# P03_Processor_1_of_3_JTAG_Header.net
KiCad netlist of a schematic drawn in Altium Designer
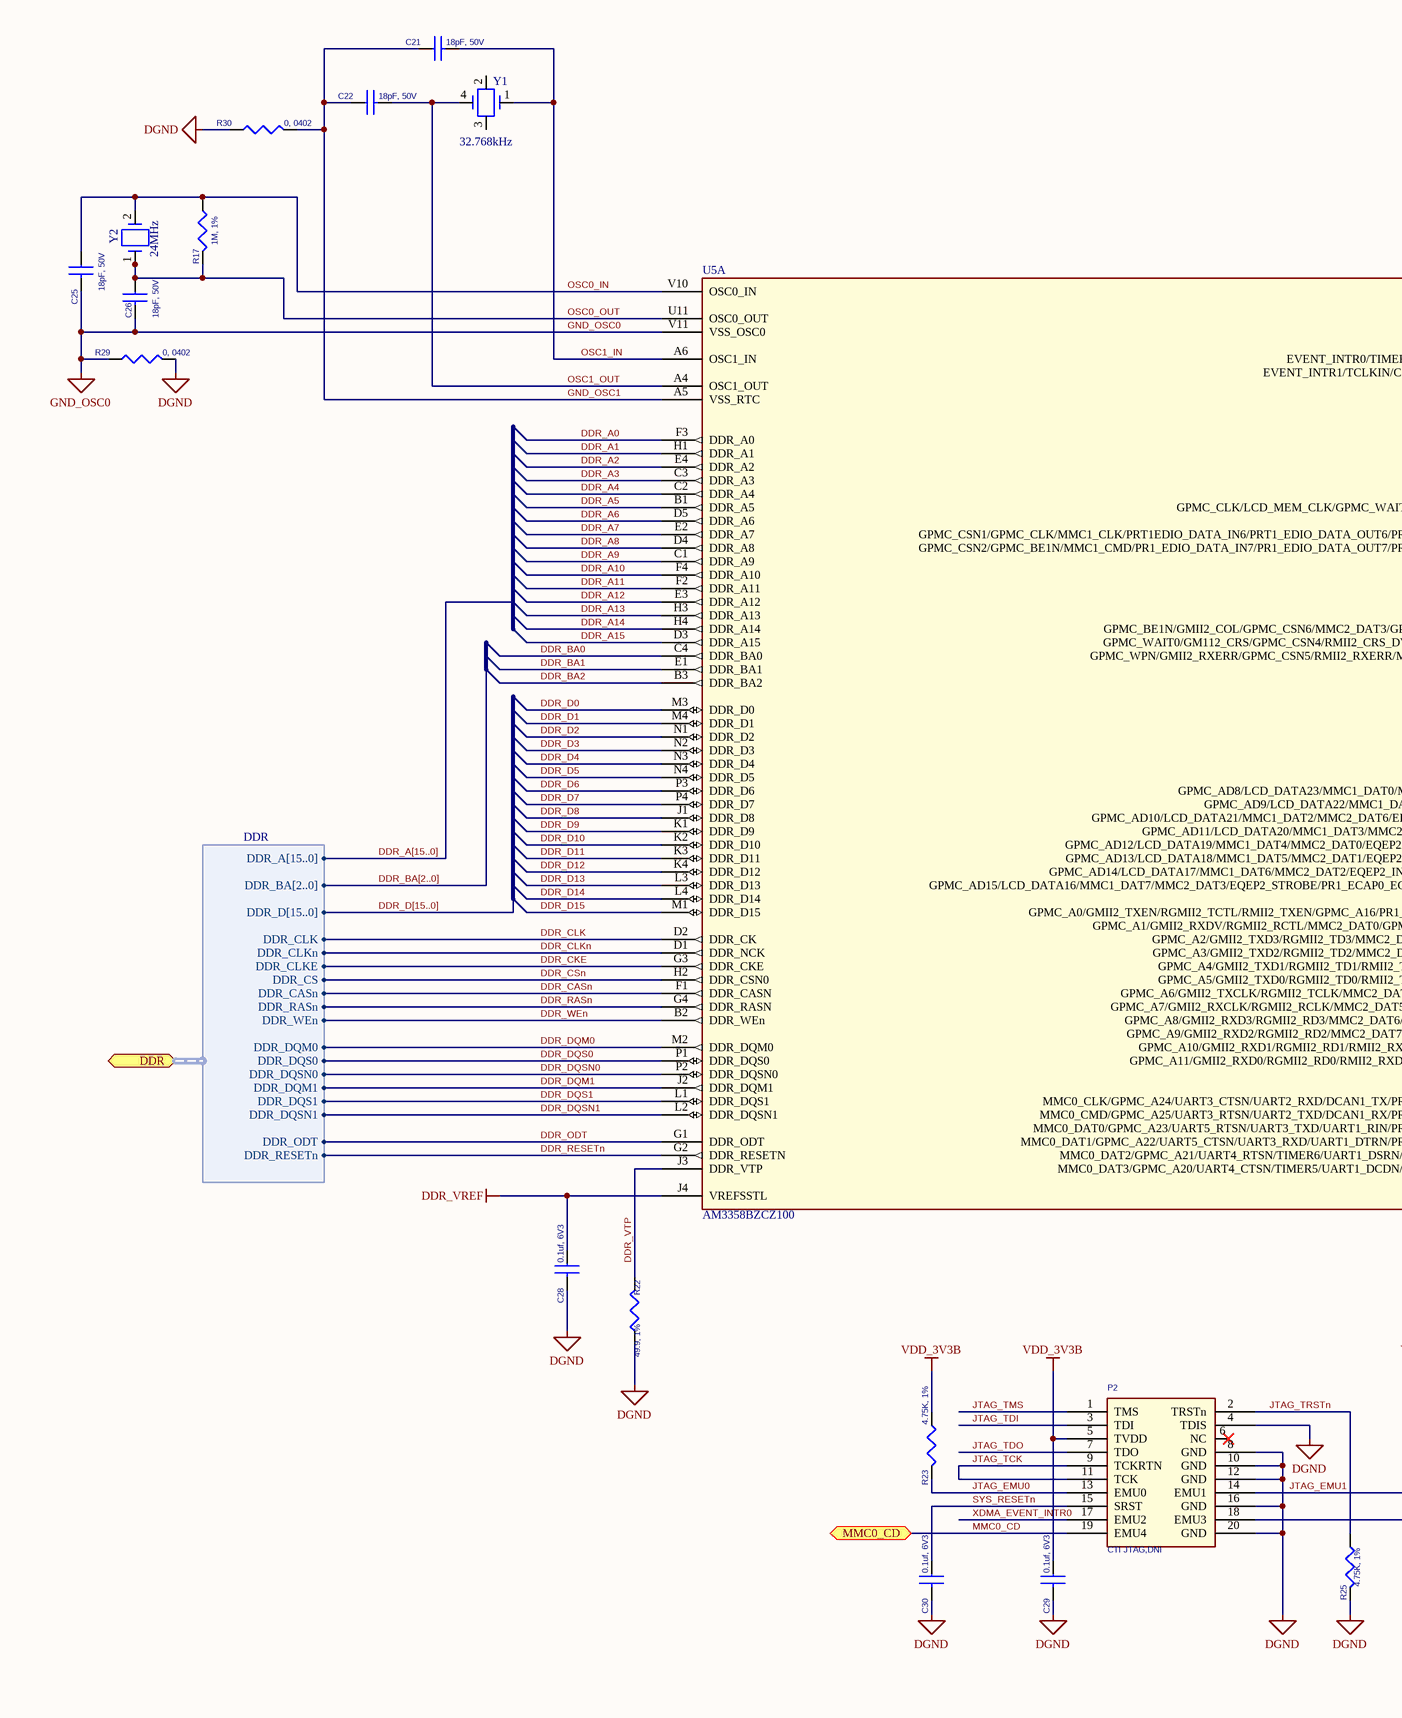
[diagram p0: P03_Processor 1 of 3, JTAG Header.SchDoc, left]
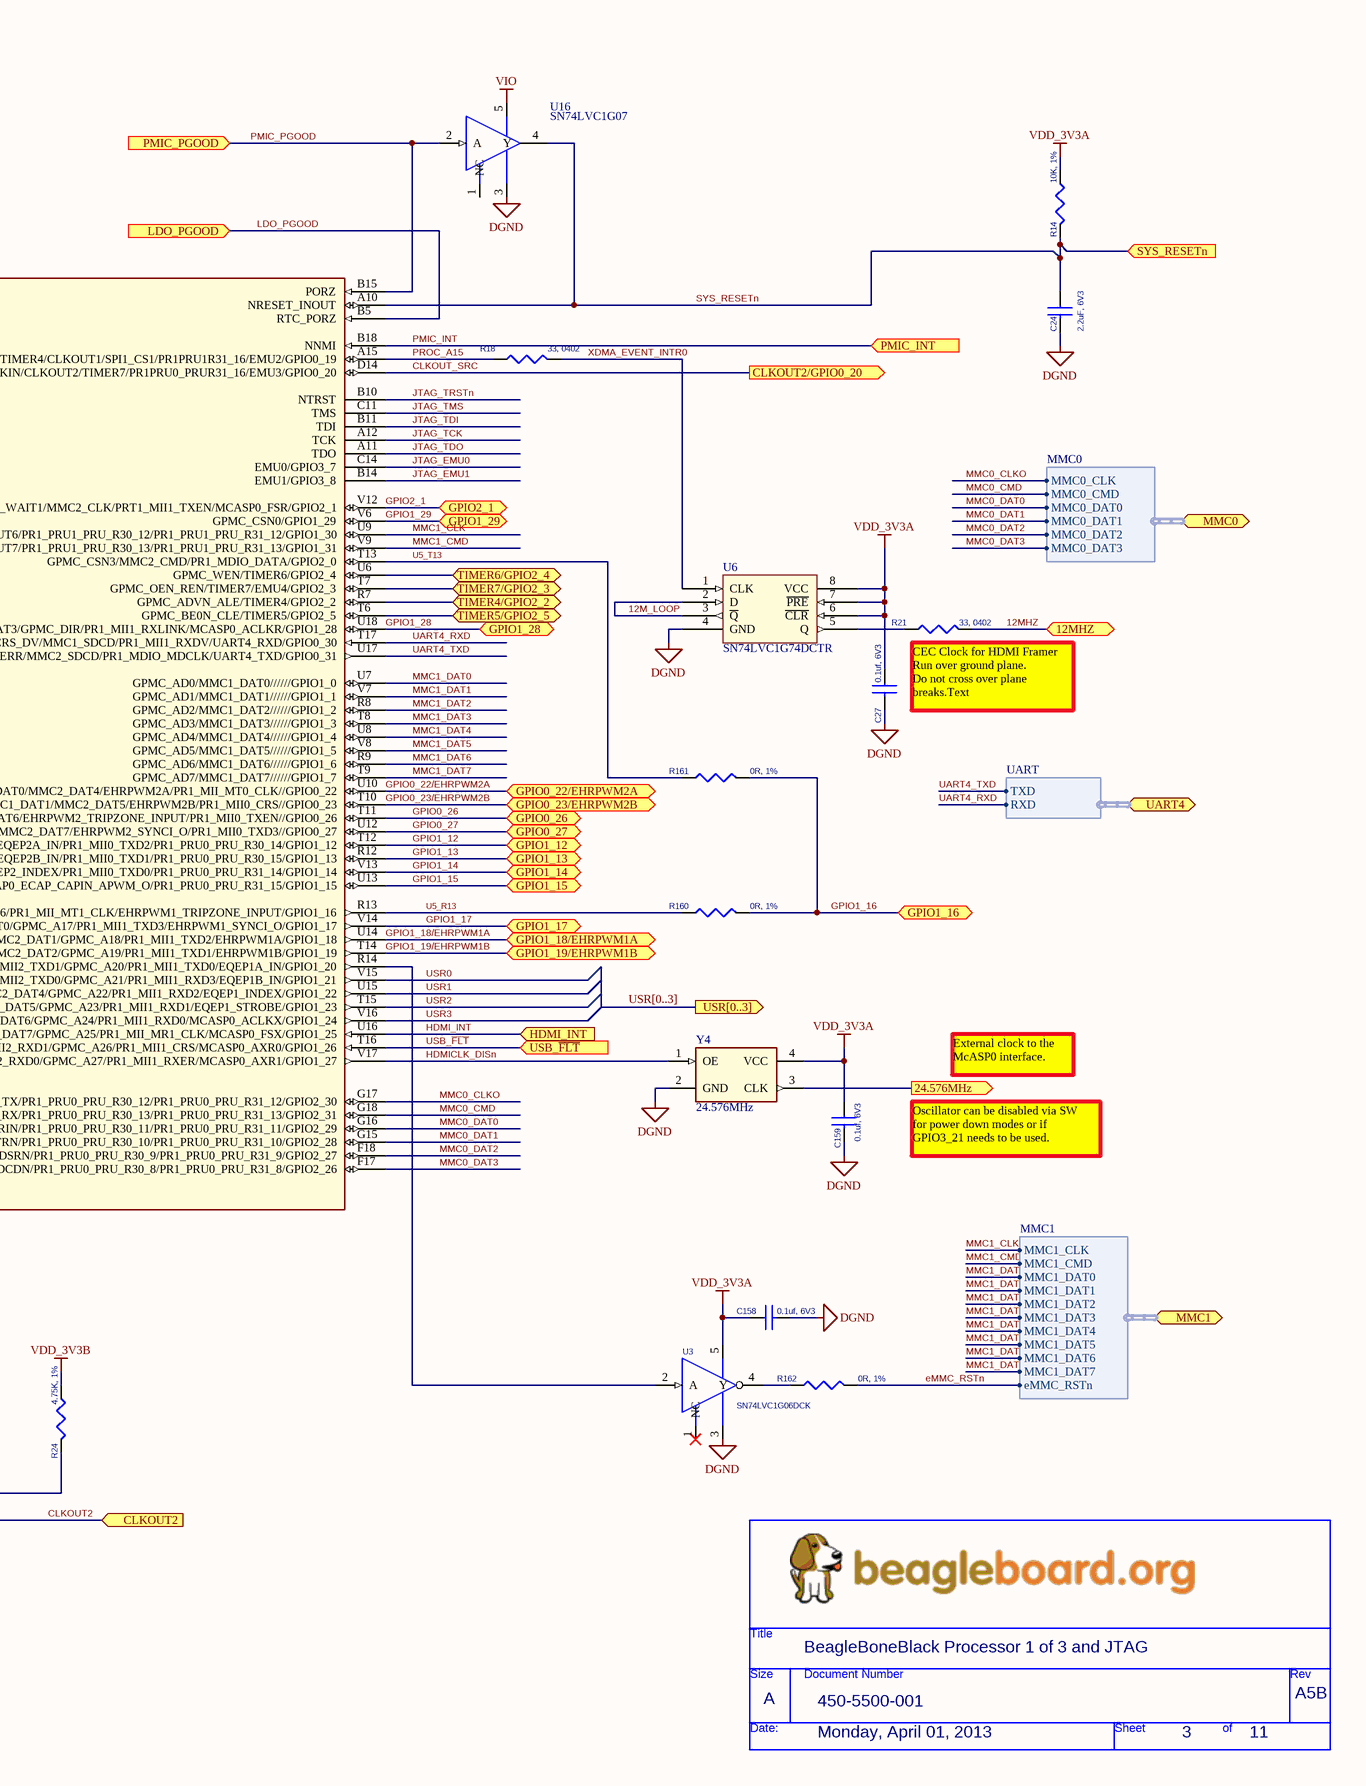
[diagram p1: P03_Processor 1 of 3, JTAG Header.SchDoc, right]

(export (version "E")
  (design (tool "Eeschema 10.0.6"))
  (components
    (comp (ref "C21")
      (value "18pF, 50V")
      (footprint "402")
      (description "CAP CER 18PF 50V 5% NP0 0402")
      (fields
        (field (name "MANUFACTURER") "TDK Corporation")
        (field (name "MANUFACTURER PART NUMBER") "C1005C0G1H180J050BA")
      )
      (libsource (lib "BEAGLEBONEBLACK_REV A5B") (part "CAP_18PF_COG_50V_5%_0402"))
    )
    (comp (ref "C22")
      (value "18pF, 50V")
      (footprint "402")
      (description "CAP CER 18PF 50V 5% NP0 0402")
      (fields
        (field (name "MANUFACTURER") "TDK Corporation")
        (field (name "MANUFACTURER PART NUMBER") "C1005C0G1H180J050BA")
      )
      (libsource (lib "BEAGLEBONEBLACK_REV A5B") (part "CAP_18PF_COG_50V_5%_0402"))
    )
    (comp (ref "C24")
      (value "2.2uF, 6V3")
      (footprint "402")
      (description "CAP CER 2.2UF 6.3V 10% X5R 0402")
      (fields
        (field (name "MANUFACTURER") "TDK Corporation")
        (field (name "MANUFACTURER PART NUMBER") "C1005X5R0J225K050BC")
      )
      (libsource (lib "BEAGLEBONEBLACK_REV A5B") (part "CAP_2.2uF_X5R_6.3V_10%_0402"))
    )
    (comp (ref "C25")
      (value "18pF, 50V")
      (footprint "402")
      (description "CAP CER 18PF 50V 5% NP0 0402")
      (fields
        (field (name "MANUFACTURER") "TDK Corporation")
        (field (name "MANUFACTURER PART NUMBER") "C1005C0G1H180J050BA")
      )
      (libsource (lib "BEAGLEBONEBLACK_REV A5B") (part "CAP_18PF_COG_50V_5%_0402"))
    )
    (comp (ref "C26")
      (value "18pF, 50V")
      (footprint "402")
      (description "CAP CER 18PF 50V 5% NP0 0402")
      (fields
        (field (name "MANUFACTURER") "TDK Corporation")
        (field (name "MANUFACTURER PART NUMBER") "C1005C0G1H180J050BA")
      )
      (libsource (lib "BEAGLEBONEBLACK_REV A5B") (part "CAP_18PF_COG_50V_5%_0402"))
    )
    (comp (ref "C27")
      (value "0.1uf, 6V3")
      (footprint "402")
      (description "CAP CER 0.1UF 6.3V 10% X5R 0402")
      (fields
        (field (name "MANUFACTURER") "TDK Corporation")
        (field (name "MANUFACTURER PART NUMBER") "C1005X5R0J104K050BA")
      )
      (libsource (lib "BEAGLEBONEBLACK_REV A5B") (part "CAP_0.1uF_X7R_16V_10% 0402"))
    )
    (comp (ref "C28")
      (value "0.1uf, 6V3")
      (footprint "402")
      (description "CAP CER 0.1UF 6.3V 10% X5R 0402")
      (fields
        (field (name "MANUFACTURER") "TDK Corporation")
        (field (name "MANUFACTURER PART NUMBER") "C1005X5R0J104K050BA")
      )
      (libsource (lib "BEAGLEBONEBLACK_REV A5B") (part "CAP_0.1uF_X7R_16V_10% 0402"))
    )
    (comp (ref "C29")
      (value "0.1uf, 6V3")
      (footprint "402")
      (description "CAP CER 0.1UF 6.3V 10% X5R 0402")
      (fields
        (field (name "MANUFACTURER") "TDK Corporation")
        (field (name "MANUFACTURER PART NUMBER") "C1005X5R0J104K050BA")
      )
      (libsource (lib "BEAGLEBONEBLACK_REV A5B") (part "CAP_0.1uF_X7R_16V_10% 0402"))
    )
    (comp (ref "C30")
      (value "0.1uf, 6V3")
      (footprint "402")
      (description "CAP CER 0.1UF 6.3V 10% X5R 0402")
      (fields
        (field (name "MANUFACTURER") "TDK Corporation")
        (field (name "MANUFACTURER PART NUMBER") "C1005X5R0J104K050BA")
      )
      (libsource (lib "BEAGLEBONEBLACK_REV A5B") (part "CAP_0.1uF_X7R_16V_10% 0402"))
    )
    (comp (ref "C158")
      (value "0.1uf, 6V3")
      (footprint "402")
      (description "CAP CER 0.1UF 6.3V 10% X5R 0402")
      (fields
        (field (name "MANUFACTURER") "TDK Corporation")
        (field (name "MANUFACTURER PART NUMBER") "C1005X5R0J104K050BA")
      )
      (libsource (lib "BEAGLEBONEBLACK_REV A5B") (part "CAP_0.1uF_X7R_16V_10% 0402"))
    )
    (comp (ref "C159")
      (value "0.1uf, 6V3")
      (footprint "402")
      (description "CAP CER 0.1UF 6.3V 10% X5R 0402")
      (fields
        (field (name "MANUFACTURER") "TDK Corporation")
        (field (name "MANUFACTURER PART NUMBER") "C1005X5R0J104K050BA")
      )
      (libsource (lib "BEAGLEBONEBLACK_REV A5B") (part "CAP_0.1uF_X7R_16V_10% 0402"))
    )
    (comp (ref "P2")
      (value "CTI JTAG,DNI")
      (description "Dual Line Header 10x2pin Tin")
      (fields
        (field (name "MANUFACTURER") "Samtec Inc")
        (field (name "MANUFACTURER PART NUMBER") "FTR-110-03-G-D-06")
      )
      (libsource (lib "BEAGLEBONEBLACK_REV A5B") (part "HDR_10x2_CJTAG"))
    )
    (comp (ref "R14")
      (value "10K, 1%")
      (footprint "402")
      (description "RES 10K OHM 1/16W 5% 0402 SMD")
      (fields
        (field (name "MANUFACTURER") "Rohm Semiconductor")
        (field (name "MANUFACTURER PART NUMBER") "MCR01MZPJ103")
      )
      (libsource (lib "BEAGLEBONEBLACK_REV A5B") (part "RES_10K_1/16W_1%_0402"))
    )
    (comp (ref "R17")
      (value "1M, 1%")
      (footprint "402")
      (description "Resistor 1Mohm 1/16W 1% 0402")
      (fields
        (field (name "MANUFACTURER") "Stackpole Electronics Inc")
        (field (name "MANUFACTURER PART NUMBER") "RMCF0402FT1M00")
      )
      (libsource (lib "BEAGLEBONEBLACK_REV A5B") (part "RES_1M_1/16W_1%_0402"))
    )
    (comp (ref "R18")
      (value "33, 0402")
      (footprint "402")
      (description "RES 33 OHM 1/16W 5% 0402 SMD")
      (fields
        (field (name "MANUFACTURER") "Panasonic Electronic Components")
        (field (name "MANUFACTURER PART NUMBER") "ERJ-2GEJ330X")
      )
      (libsource (lib "BEAGLEBONEBLACK_REV A5B") (part "RES_33_0402"))
    )
    (comp (ref "R21")
      (value "33, 0402")
      (footprint "402")
      (description "RES 33 OHM 1/16W 5% 0402 SMD")
      (fields
        (field (name "MANUFACTURER") "Panasonic Electronic Components")
        (field (name "MANUFACTURER PART NUMBER") "ERJ-2GEJ330X")
      )
      (libsource (lib "BEAGLEBONEBLACK_REV A5B") (part "RES_33_0402"))
    )
    (comp (ref "R22")
      (value "49.9, 1%")
      (footprint "402")
      (description "RES 49.9 OHM 1/16W 1% 0402 SMD")
      (fields
        (field (name "MANUFACTURER") "Yageo")
        (field (name "MANUFACTURER PART NUMBER") "RC0402FR-0749R9L")
      )
      (libsource (lib "BEAGLEBONEBLACK_REV A5B") (part "RES_4.7K_0402"))
    )
    (comp (ref "R23")
      (value "4.75K, 1%")
      (footprint "402")
      (description "RES 4.75K 1/16W 1% 0402 SMD")
      (fields
        (field (name "MANUFACTURER") "Stackpole Electronics Inc")
        (field (name "MANUFACTURER PART NUMBER") "RMCF0402FT4K75")
      )
      (libsource (lib "BEAGLEBONEBLACK_REV A5B") (part "RES_4.7K_0402"))
    )
    (comp (ref "R24")
      (value "4.75K, 1%")
      (footprint "402")
      (description "RES 4.75K 1/16W 1% 0402 SMD")
      (fields
        (field (name "MANUFACTURER") "Stackpole Electronics Inc")
        (field (name "MANUFACTURER PART NUMBER") "RMCF0402FT4K75")
      )
      (libsource (lib "BEAGLEBONEBLACK_REV A5B") (part "RES_4.7K_0402"))
    )
    (comp (ref "R25")
      (value "4.75K, 1%")
      (footprint "402")
      (description "RES 4.75K 1/16W 1% 0402 SMD")
      (fields
        (field (name "MANUFACTURER") "Stackpole Electronics Inc")
        (field (name "MANUFACTURER PART NUMBER") "RMCF0402FT4K75")
      )
      (libsource (lib "BEAGLEBONEBLACK_REV A5B") (part "RES_4.7K_0402"))
    )
    (comp (ref "R29")
      (value "0, 0402")
      (footprint "402")
      (description "RES 0 OHM 1/16W 5% 0402 SMD")
      (fields
        (field (name "MANUFACTURER") "Panasonic Electronic Components")
        (field (name "MANUFACTURER PART NUMBER") "ERJ-2GEJ330X")
      )
      (libsource (lib "BEAGLEBONEBLACK_REV A5B") (part "RES_33_0402"))
    )
    (comp (ref "R30")
      (value "0, 0402")
      (footprint "402")
      (description "RES 0 OHM 1/16W 5% 0402 SMD")
      (fields
        (field (name "MANUFACTURER") "Panasonic Electronic Components")
        (field (name "MANUFACTURER PART NUMBER") "ERJ-2GEJ330X")
      )
      (libsource (lib "BEAGLEBONEBLACK_REV A5B") (part "RES_33_0402"))
    )
    (comp (ref "R160")
      (value "0R, 1%")
      (footprint "402")
      (description "RES 0.0 OHM 1/16W 0402 SMD")
      (fields
        (field (name "MANUFACTURER") "Yageo")
        (field (name "MANUFACTURER PART NUMBER") "RC0402JR-070RL")
      )
      (libsource (lib "BEAGLEBONEBLACK_REV A5B") (part "RES_0_1/16W_1%_0402"))
    )
    (comp (ref "R161")
      (value "0R, 1%")
      (footprint "402")
      (description "RES 0.0 OHM 1/16W 0402 SMD")
      (fields
        (field (name "MANUFACTURER") "Yageo")
        (field (name "MANUFACTURER PART NUMBER") "RC0402JR-070RL")
      )
      (libsource (lib "BEAGLEBONEBLACK_REV A5B") (part "RES_0_1/16W_1%_0402"))
    )
    (comp (ref "R162")
      (value "0R, 1%")
      (footprint "402")
      (description "RES 0.0 OHM 1/16W 0402 SMD")
      (fields
        (field (name "MANUFACTURER") "Yageo")
        (field (name "MANUFACTURER PART NUMBER") "RC0402JR-070RL")
      )
      (libsource (lib "BEAGLEBONEBLACK_REV A5B") (part "RES_0_1/16W_1%_0402"))
    )
    (comp (ref "U3")
      (value "SN74LVC1G06DCK")
      (footprint "DCK5_2P15X1P4")
      (description "IC INVERTER SINGLE 1INPUT SC705")
      (fields
        (field (name "MANUFACTURER") "Texas Instruments")
        (field (name "MANUFACTURER PART NUMBER") "SN74LVC1G06DCKTG4")
      )
      (libsource (lib "BEAGLEBONEBLACK_REV A5B") (part "SN74LVC1G06DCK"))
    )
    (comp (ref "U5")
      (value "AM3358BZCZ100")
      (footprint "am33xx_15x15")
      (description "IC MPU SITARA 1.0GHZ 324NFBGA")
      (fields
        (field (name "MANUFACTURER") "Texas Instruments")
        (field (name "MANUFACTURER PART NUMBER") "XAM3359ZCZ")
      )
      (libsource (lib "BEAGLEBONEBLACK_REV A5B") (part "IC_AM335X_ZCE_1"))
    )
    (comp (ref "U6")
      (value "SN74LVC1G74DCTR")
      (footprint "SOP8_DCT")
      (description "SINGLE  POSITIVE-EDGE-TRIGGERED  D-TYPE  FLIP-FLOP WITH  CLEAR  AND  PRESET")
      (fields (field (name "MANUFACTURER") "Texas Instruments"))
      (libsource (lib "BEAGLEBONEBLACK_REV A5B") (part "SN74LVC1G74DCTR"))
    )
    (comp (ref "U16")
      (value "SN74LVC1G07")
      (footprint "DCK5_2P15X1P4")
      (description "IC BUFFER SINGLE 1INPUT SC705")
      (fields
        (field (name "MANUFACTURER") "Texas Instruments")
        (field (name "MANUFACTURER PART NUMBER") "SN74LVC1G06DCKTG4")
      )
      (libsource (lib "BEAGLEBONEBLACK_REV A5B_1") (part "SN74LVC1G07DCK"))
    )
    (comp (ref "Y1")
      (value "32.768kHz")
      (footprint "XTAL4_126-216SMD")
      (description "CRYSTAL 32.768KHZ 12.5PF SMD")
      (fields
        (field (name "MANUFACTURER") "Citizen Finetech Miyota")
        (field (name "MANUFACTURER PART NUMBER") "CM200C-32.768KAZF-UT")
      )
      (libsource (lib "BEAGLEBONEBLACK_REV A5B") (part "CRYS_32_768KHz_SMD32"))
    )
    (comp (ref "Y2")
      (value "24MHz")
      (footprint "XTAL150SMD_125X196")
      (description "CRYSTAL 24.000MHZ 18PF SMD")
      (fields
        (field (name "MANUFACTURER") "TXC CORPORATION")
        (field (name "MANUFACTURER PART NUMBER") "7A-24.000MAAJ-T")
      )
      (libsource (lib "BEAGLEBONEBLACK_REV A5B") (part "CRYS_24MHz_SCC"))
    )
    (comp (ref "Y4")
      (value "24.576MHz")
      (footprint "OSC4_61X65LS_79X98SMD")
      (fields
        (field (name "MANUFACTURER") "Abracon Corporation")
        (field (name "MANUFACTURER PART NUMBER") "ASDMB-24.576MHZ-LC-T")
      )
      (libsource (lib "BEAGLEBONEBLACK_REV A5B") (part "ASDMB"))
    )
  )
  (nets
    (net (code "5") (name "/12MHZ") (class "Default")
      (node (ref "R21") (pin "2") (pinfunction "2_2") (pintype "passive"))
    )
    (net (code "6") (name "/12M_LOOP") (class "Default")
      (node (ref "U6") (pin "2") (pinfunction "D_2") (pintype "input"))
      (node (ref "U6") (pin "3") (pinfunction "~{Q}_3") (pintype "output"))
    )
    (net (code "7") (name "/24.576MHz") (class "Default")
      (node (ref "Y4") (pin "3") (pinfunction "CLK_3") (pintype "output"))
    )
    (net (code "8") (name "/CLKOUT2") (class "Default")
      (node (ref "P2") (pin "18") (pinfunction "EMU3_18") (pintype "passive"))
    )
    (net (code "9") (name "/CLKOUT_SRC") (class "Default")
      (node (ref "U5") (pin "D14") (pinfunction "EVENT_INTR1/TCLKIN/CLKOUT2/TIMER7/PR1PRU0_PRUR31_16/EMU3/GPIO0_20_D14") (pintype "bidirectional"))
    )
    (net (code "10") (name "/DDR_A0") (class "Default")
      (node (ref "U5") (pin "F3") (pinfunction "DDR_A0_F3") (pintype "output"))
    )
    (net (code "11") (name "/DDR_A1") (class "Default")
      (node (ref "U5") (pin "H1") (pinfunction "DDR_A1_H1") (pintype "output"))
    )
    (net (code "12") (name "/DDR_A2") (class "Default")
      (node (ref "U5") (pin "E4") (pinfunction "DDR_A2_E4") (pintype "output"))
    )
    (net (code "13") (name "/DDR_A3") (class "Default")
      (node (ref "U5") (pin "C3") (pinfunction "DDR_A3_C3") (pintype "output"))
    )
    (net (code "14") (name "/DDR_A4") (class "Default")
      (node (ref "U5") (pin "C2") (pinfunction "DDR_A4_C2") (pintype "output"))
    )
    (net (code "15") (name "/DDR_A5") (class "Default")
      (node (ref "U5") (pin "B1") (pinfunction "DDR_A5_B1") (pintype "output"))
    )
    (net (code "16") (name "/DDR_A6") (class "Default")
      (node (ref "U5") (pin "D5") (pinfunction "DDR_A6_D5") (pintype "output"))
    )
    (net (code "17") (name "/DDR_A7") (class "Default")
      (node (ref "U5") (pin "E2") (pinfunction "DDR_A7_E2") (pintype "output"))
    )
    (net (code "18") (name "/DDR_A8") (class "Default")
      (node (ref "U5") (pin "D4") (pinfunction "DDR_A8_D4") (pintype "output"))
    )
    (net (code "19") (name "/DDR_A9") (class "Default")
      (node (ref "U5") (pin "C1") (pinfunction "DDR_A9_C1") (pintype "output"))
    )
    (net (code "20") (name "/DDR_A10") (class "Default")
      (node (ref "U5") (pin "F4") (pinfunction "DDR_A10_F4") (pintype "output"))
    )
    (net (code "21") (name "/DDR_A11") (class "Default")
      (node (ref "U5") (pin "F2") (pinfunction "DDR_A11_F2") (pintype "output"))
    )
    (net (code "22") (name "/DDR_A12") (class "Default")
      (node (ref "U5") (pin "E3") (pinfunction "DDR_A12_E3") (pintype "output"))
    )
    (net (code "23") (name "/DDR_A13") (class "Default")
      (node (ref "U5") (pin "H3") (pinfunction "DDR_A13_H3") (pintype "output"))
    )
    (net (code "24") (name "/DDR_A14") (class "Default")
      (node (ref "U5") (pin "H4") (pinfunction "DDR_A14_H4") (pintype "output"))
    )
    (net (code "25") (name "/DDR_A15") (class "Default")
      (node (ref "U5") (pin "D3") (pinfunction "DDR_A15_D3") (pintype "output"))
    )
    (net (code "27") (name "/DDR_BA0") (class "Default")
      (node (ref "U5") (pin "C4") (pinfunction "DDR_BA0_C4") (pintype "output"))
    )
    (net (code "28") (name "/DDR_BA1") (class "Default")
      (node (ref "U5") (pin "E1") (pinfunction "DDR_BA1_E1") (pintype "output"))
    )
    (net (code "29") (name "/DDR_BA2") (class "Default")
      (node (ref "U5") (pin "B3") (pinfunction "DDR_BA2_B3") (pintype "output"))
    )
    (net (code "31") (name "/DDR_CASn") (class "Default")
      (node (ref "U5") (pin "F1") (pinfunction "DDR_CASN_F1") (pintype "output"))
    )
    (net (code "32") (name "/DDR_CKE") (class "Default")
      (node (ref "U5") (pin "G3") (pinfunction "DDR_CKE_G3") (pintype "output"))
    )
    (net (code "33") (name "/DDR_CLK") (class "Default")
      (node (ref "U5") (pin "D2") (pinfunction "DDR_CK_D2") (pintype "output"))
    )
    (net (code "34") (name "/DDR_CLKn") (class "Default")
      (node (ref "U5") (pin "D1") (pinfunction "DDR_NCK_D1") (pintype "output"))
    )
    (net (code "35") (name "/DDR_CSn") (class "Default")
      (node (ref "U5") (pin "H2") (pinfunction "DDR_CSN0_H2") (pintype "output"))
    )
    (net (code "36") (name "/DDR_D0") (class "Default")
      (node (ref "U5") (pin "M3") (pinfunction "DDR_D0_M3") (pintype "bidirectional"))
    )
    (net (code "37") (name "/DDR_D1") (class "Default")
      (node (ref "U5") (pin "M4") (pinfunction "DDR_D1_M4") (pintype "bidirectional"))
    )
    (net (code "38") (name "/DDR_D2") (class "Default")
      (node (ref "U5") (pin "N1") (pinfunction "DDR_D2_N1") (pintype "bidirectional"))
    )
    (net (code "39") (name "/DDR_D3") (class "Default")
      (node (ref "U5") (pin "N2") (pinfunction "DDR_D3_N2") (pintype "bidirectional"))
    )
    (net (code "40") (name "/DDR_D4") (class "Default")
      (node (ref "U5") (pin "N3") (pinfunction "DDR_D4_N3") (pintype "bidirectional"))
    )
    (net (code "41") (name "/DDR_D5") (class "Default")
      (node (ref "U5") (pin "N4") (pinfunction "DDR_D5_N4") (pintype "bidirectional"))
    )
    (net (code "42") (name "/DDR_D6") (class "Default")
      (node (ref "U5") (pin "P3") (pinfunction "DDR_D6_P3") (pintype "bidirectional"))
    )
    (net (code "43") (name "/DDR_D7") (class "Default")
      (node (ref "U5") (pin "P4") (pinfunction "DDR_D7_P4") (pintype "bidirectional"))
    )
    (net (code "44") (name "/DDR_D8") (class "Default")
      (node (ref "U5") (pin "J1") (pinfunction "DDR_D8_J1") (pintype "bidirectional"))
    )
    (net (code "45") (name "/DDR_D9") (class "Default")
      (node (ref "U5") (pin "K1") (pinfunction "DDR_D9_K1") (pintype "bidirectional"))
    )
    (net (code "46") (name "/DDR_D10") (class "Default")
      (node (ref "U5") (pin "K2") (pinfunction "DDR_D10_K2") (pintype "bidirectional"))
    )
    (net (code "47") (name "/DDR_D11") (class "Default")
      (node (ref "U5") (pin "K3") (pinfunction "DDR_D11_K3") (pintype "bidirectional"))
    )
    (net (code "48") (name "/DDR_D12") (class "Default")
      (node (ref "U5") (pin "K4") (pinfunction "DDR_D12_K4") (pintype "bidirectional"))
    )
    (net (code "49") (name "/DDR_D13") (class "Default")
      (node (ref "U5") (pin "L3") (pinfunction "DDR_D13_L3") (pintype "bidirectional"))
    )
    (net (code "50") (name "/DDR_D14") (class "Default")
      (node (ref "U5") (pin "L4") (pinfunction "DDR_D14_L4") (pintype "bidirectional"))
    )
    (net (code "51") (name "/DDR_D15") (class "Default")
      (node (ref "U5") (pin "M1") (pinfunction "DDR_D15_M1") (pintype "bidirectional"))
    )
    (net (code "52") (name "/DDR_DQM0") (class "Default")
      (node (ref "U5") (pin "M2") (pinfunction "DDR_DQM0_M2") (pintype "output"))
    )
    (net (code "53") (name "/DDR_DQM1") (class "Default")
      (node (ref "U5") (pin "J2") (pinfunction "DDR_DQM1_J2") (pintype "output"))
    )
    (net (code "54") (name "/DDR_DQS0") (class "Default")
      (node (ref "U5") (pin "P1") (pinfunction "DDR_DQS0_P1") (pintype "bidirectional"))
    )
    (net (code "55") (name "/DDR_DQS1") (class "Default")
      (node (ref "U5") (pin "L1") (pinfunction "DDR_DQS1_L1") (pintype "bidirectional"))
    )
    (net (code "56") (name "/DDR_DQSN0") (class "Default")
      (node (ref "U5") (pin "P2") (pinfunction "DDR_DQSN0_P2") (pintype "bidirectional"))
    )
    (net (code "57") (name "/DDR_DQSN1") (class "Default")
      (node (ref "U5") (pin "L2") (pinfunction "DDR_DQSN1_L2") (pintype "bidirectional"))
    )
    (net (code "59") (name "/DDR_ODT") (class "Default")
      (node (ref "U5") (pin "G1") (pinfunction "DDR_ODT_G1") (pintype "passive"))
    )
    (net (code "60") (name "/DDR_RASn") (class "Default")
      (node (ref "U5") (pin "G4") (pinfunction "DDR_RASN_G4") (pintype "output"))
    )
    (net (code "61") (name "/DDR_RESETn") (class "Default")
      (node (ref "U5") (pin "G2") (pinfunction "DDR_RESETN_G2") (pintype "output"))
    )
    (net (code "62") (name "/DDR_VTP") (class "Default")
      (node (ref "R22") (pin "2") (pinfunction "2_2") (pintype "passive"))
      (node (ref "U5") (pin "J3") (pinfunction "DDR_VTP_J3") (pintype "passive"))
    )
    (net (code "63") (name "/DDR_WEn") (class "Default")
      (node (ref "U5") (pin "B2") (pinfunction "DDR_WEn_B2") (pintype "output"))
    )
    (net (code "64") (name "/GND_OSC1") (class "Default")
      (node (ref "C21") (pin "1") (pinfunction "1_1") (pintype "passive"))
      (node (ref "C22") (pin "1") (pinfunction "1_1") (pintype "passive"))
      (node (ref "R30") (pin "2") (pinfunction "2_2") (pintype "passive"))
      (node (ref "U5") (pin "A5") (pinfunction "VSS_RTC_A5") (pintype "power_in"))
    )
    (net (code "65") (name "/GPIO0_22{slash}EHRPWM2A") (class "Default")
      (node (ref "U5") (pin "U10") (pinfunction "GPMC_AD8/LCD_DATA23/MMC1_DAT0/MMC2_DAT4/EHRPWM2A/PR1_MII_MT0_CLK//GPIO0_22_U10") (pintype "bidirectional"))
    )
    (net (code "66") (name "/GPIO0_23{slash}EHRPWM2B") (class "Default")
      (node (ref "U5") (pin "T10") (pinfunction "GPMC_AD9/LCD_DATA22/MMC1_DAT1/MMC2_DAT5/EHRPWM2B/PR1_MII0_CRS//GPIO0_23_T10") (pintype "bidirectional"))
    )
    (net (code "67") (name "/GPIO0_26") (class "Default")
      (node (ref "U5") (pin "T11") (pinfunction "GPMC_AD10/LCD_DATA21/MMC1_DAT2/MMC2_DAT6/EHRPWM2_TRIPZONE_INPUT/PR1_MII0_TXEN//GPIO0_26_T11") (pintype "bidirectional"))
    )
    (net (code "68") (name "/GPIO0_27") (class "Default")
      (node (ref "U5") (pin "U12") (pinfunction "GPMC_AD11/LCD_DATA20/MMC1_DAT3/MMC2_DAT7/EHRPWM2_SYNCI_O/PR1_MII0_TXD3//GPIO0_27_U12") (pintype "bidirectional"))
    )
    (net (code "69") (name "/GPIO1_12") (class "Default")
      (node (ref "U5") (pin "T12") (pinfunction "GPMC_AD12/LCD_DATA19/MMC1_DAT4/MMC2_DAT0/EQEP2A_IN/PR1_MII0_TXD2/PR1_PRU0_PRU_R30_14/GPIO1_12_T12") (pintype "bidirectional"))
    )
    (net (code "70") (name "/GPIO1_13") (class "Default")
      (node (ref "U5") (pin "R12") (pinfunction "GPMC_AD13/LCD_DATA18/MMC1_DAT5/MMC2_DAT1/EQEP2B_IN/PR1_MII0_TXD1/PR1_PRU0_PRU_R30_15/GPIO1_13_R12") (pintype "bidirectional"))
    )
    (net (code "71") (name "/GPIO1_14") (class "Default")
      (node (ref "U5") (pin "V13") (pinfunction "GPMC_AD14/LCD_DATA17/MMC1_DAT6/MMC2_DAT2/EQEP2_INDEX/PR1_MII0_TXD0/PR1_PRU0_PRU_R31_14/GPIO1_14_V13") (pintype "bidirectional"))
    )
    (net (code "72") (name "/GPIO1_15") (class "Default")
      (node (ref "U5") (pin "U13") (pinfunction "GPMC_AD15/LCD_DATA16/MMC1_DAT7/MMC2_DAT3/EQEP2_STROBE/PR1_ECAP0_ECAP_CAPIN_APWM_O/PR1_PRU0_PRU_R31_15/GPIO1_15_U13") (pintype "bidirectional"))
    )
    (net (code "73") (name "/GPIO1_16") (class "Default")
      (node (ref "R160") (pin "2") (pinfunction "2_2") (pintype "passive"))
      (node (ref "R161") (pin "2") (pinfunction "2_2") (pintype "passive"))
    )
    (net (code "74") (name "/GPIO1_17") (class "Default")
      (node (ref "U5") (pin "V14") (pinfunction "GPMC_A1/GMII2_RXDV/RGMII2_RCTL/MMC2_DAT0/GPMC_A17/PR1_MII1_TXD3/EHRPWM1_SYNCI_O/GPIO1_17_V14") (pintype "output"))
    )
    (net (code "75") (name "/GPIO1_18{slash}EHRPWM1A") (class "Default")
      (node (ref "U5") (pin "U14") (pinfunction "GPMC_A2/GMII2_TXD3/RGMII2_TD3/MMC2_DAT1/GPMC_A18/PR1_MII1_TXD2/EHRPWM1A/GPIO1_18_U14") (pintype "output"))
    )
    (net (code "76") (name "/GPIO1_19{slash}EHRPWM1B") (class "Default")
      (node (ref "U5") (pin "T14") (pinfunction "GPMC_A3/GMII2_TXD2/RGMII2_TD2/MMC2_DAT2/GPMC_A19/PR1_MII1_TXD1/EHRPWM1B/GPIO1_19_T14") (pintype "output"))
    )
    (net (code "77") (name "/GPIO1_28") (class "Default")
      (node (ref "U5") (pin "U18") (pinfunction "GPMC_BE1N/GMII2_COL/GPMC_CSN6/MMC2_DAT3/GPMC_DIR/PR1_MII1_RXLINK/MCASP0_ACLKR/GPIO1_28_U18") (pintype "bidirectional"))
    )
    (net (code "78") (name "/GPIO1_29") (class "Default")
      (node (ref "U5") (pin "V6") (pinfunction "GPMC_CSN0/GPIO1_29_V6") (pintype "bidirectional"))
    )
    (net (code "79") (name "/GPIO2_1") (class "Default")
      (node (ref "U5") (pin "V12") (pinfunction "GPMC_CLK/LCD_MEM_CLK/GPMC_WAIT1/MMC2_CLK/PRT1_MII1_TXEN/MCASP0_FSR/GPIO2_1_V12") (pintype "bidirectional"))
    )
    (net (code "80") (name "/HDMICLK_DISn") (class "Default")
      (node (ref "U5") (pin "V17") (pinfunction "GPMC_A11/GMII2_RXD0/RGMII2_RD0/RMII2_RXD0/GPMC_A27/PR1_MII1_RXER/MCASP0_AXR1/GPIO1_27_V17") (pintype "output"))
      (node (ref "Y4") (pin "1") (pinfunction "OE_1") (pintype "input"))
    )
    (net (code "81") (name "/HDMI_INT") (class "Default")
      (node (ref "U5") (pin "U16") (pinfunction "GPMC_A9/GMII2_RXD2/RGMII2_RD2/MMC2_DAT7/GPMC_A25/PR1_MII_MR1_CLK/MCASP0_FSX/GPIO1_25_U16") (pintype "input"))
    )
    (net (code "82") (name "/JTAG_EMU0") (class "Default")
      (node (ref "P2") (pin "13") (pinfunction "EMU0_13") (pintype "passive"))
      (node (ref "R23") (pin "2") (pinfunction "2_2") (pintype "passive"))
      (node (ref "U5") (pin "C14") (pinfunction "EMU0/GPIO3_7_C14") (pintype "passive"))
    )
    (net (code "83") (name "/JTAG_EMU1") (class "Default")
      (node (ref "P2") (pin "14") (pinfunction "EMU1_14") (pintype "passive"))
      (node (ref "R24") (pin "2") (pinfunction "2_2") (pintype "passive"))
      (node (ref "U5") (pin "B14") (pinfunction "EMU1/GPIO3_8_B14") (pintype "passive"))
    )
    (net (code "84") (name "/JTAG_TCK") (class "Default")
      (node (ref "P2") (pin "11") (pinfunction "TCK_11") (pintype "passive"))
      (node (ref "P2") (pin "9") (pinfunction "TCKRTN_9") (pintype "passive"))
      (node (ref "U5") (pin "A12") (pinfunction "TCK_A12") (pintype "passive"))
    )
    (net (code "85") (name "/JTAG_TDI") (class "Default")
      (node (ref "P2") (pin "3") (pinfunction "TDI_3") (pintype "passive"))
      (node (ref "U5") (pin "B11") (pinfunction "TDI_B11") (pintype "passive"))
    )
    (net (code "86") (name "/JTAG_TDO") (class "Default")
      (node (ref "P2") (pin "7") (pinfunction "TDO_7") (pintype "passive"))
      (node (ref "U5") (pin "A11") (pinfunction "TDO_A11") (pintype "passive"))
    )
    (net (code "87") (name "/JTAG_TMS") (class "Default")
      (node (ref "P2") (pin "1") (pinfunction "TMS_1") (pintype "passive"))
      (node (ref "U5") (pin "C11") (pinfunction "TMS_C11") (pintype "passive"))
    )
    (net (code "88") (name "/JTAG_TRSTn") (class "Default")
      (node (ref "P2") (pin "2") (pinfunction "TRSTn_2") (pintype "passive"))
      (node (ref "R25") (pin "1") (pinfunction "1_1") (pintype "passive"))
      (node (ref "U5") (pin "B10") (pinfunction "NTRST_B10") (pintype "passive"))
    )
    (net (code "89") (name "/LDO_PGOOD") (class "Default")
      (node (ref "U5") (pin "B5") (pinfunction "RTC_PORZ_B5") (pintype "input"))
    )
    (net (code "90") (name "/MMC0_CD") (class "Default")
      (node (ref "P2") (pin "19") (pinfunction "EMU4_19") (pintype "passive"))
    )
    (net (code "91") (name "/MMC0_CLKO") (class "Default")
      (node (ref "U5") (pin "G17") (pinfunction "MMC0_CLK/GPMC_A24/UART3_CTSN/UART2_RXD/DCAN1_TX/PR1_PRU0_PRU_R30_12/PR1_PRU0_PRU_R31_12/GPIO2_30_G17") (pintype "bidirectional"))
    )
    (net (code "92") (name "/MMC0_CMD") (class "Default")
      (node (ref "U5") (pin "G18") (pinfunction "MMC0_CMD/GPMC_A25/UART3_RTSN/UART2_TXD/DCAN1_RX/PR1_PRU0_PRU_R30_13/PR1_PRU0_PRU_R31_13/GPIO2_31_G18") (pintype "bidirectional"))
    )
    (net (code "93") (name "/MMC0_DAT0") (class "Default")
      (node (ref "U5") (pin "G16") (pinfunction "MMC0_DAT0/GPMC_A23/UART5_RTSN/UART3_TXD/UART1_RIN/PR1_PRU0_PRU_R30_11/PR1_PRU0_PRU_R31_11/GPIO2_29_G16") (pintype "bidirectional"))
    )
    (net (code "94") (name "/MMC0_DAT1") (class "Default")
      (node (ref "U5") (pin "G15") (pinfunction "MMC0_DAT1/GPMC_A22/UART5_CTSN/UART3_RXD/UART1_DTRN/PR1_PRU0_PRU_R30_10/PR1_PRU0_PRU_R31_10/GPIO2_28_G15") (pintype "bidirectional"))
    )
    (net (code "95") (name "/MMC0_DAT2") (class "Default")
      (node (ref "U5") (pin "F18") (pinfunction "MMC0_DAT2/GPMC_A21/UART4_RTSN/TIMER6/UART1_DSRN/PR1_PRU0_PRU_R30_9/PR1_PRU0_PRU_R31_9/GPIO2_27_F18") (pintype "bidirectional"))
    )
    (net (code "96") (name "/MMC0_DAT3") (class "Default")
      (node (ref "U5") (pin "F17") (pinfunction "MMC0_DAT3/GPMC_A20/UART4_CTSN/TIMER5/UART1_DCDN/PR1_PRU0_PRU_R30_8/PR1_PRU0_PRU_R31_8/GPIO2_26_F17") (pintype "bidirectional"))
    )
    (net (code "97") (name "/MMC1_CLK") (class "Default")
      (node (ref "U5") (pin "U9") (pinfunction "GPMC_CSN1/GPMC_CLK/MMC1_CLK/PRT1EDIO_DATA_IN6/PRT1_EDIO_DATA_OUT6/PR1_PRU1_PRU_R30_12/PR1_PRU1_PRU_R31_12/GPIO1_30_U9") (pintype "bidirectional"))
    )
    (net (code "98") (name "/MMC1_CMD") (class "Default")
      (node (ref "U5") (pin "V9") (pinfunction "GPMC_CSN2/GPMC_BE1N/MMC1_CMD/PR1_EDIO_DATA_IN7/PR1_EDIO_DATA_OUT7/PR1_PRU1_PRU_R30_13/PR1_PRU1_PRU_R31_13/GPIO1_31_V9") (pintype "bidirectional"))
    )
    (net (code "99") (name "/MMC1_DAT0") (class "Default")
      (node (ref "U5") (pin "U7") (pinfunction "GPMC_AD0/MMC1_DAT0//////GPIO1_0_U7") (pintype "bidirectional"))
    )
    (net (code "100") (name "/MMC1_DAT1") (class "Default")
      (node (ref "U5") (pin "V7") (pinfunction "GPMC_AD1/MMC1_DAT1//////GPIO1_1_V7") (pintype "bidirectional"))
    )
    (net (code "101") (name "/MMC1_DAT2") (class "Default")
      (node (ref "U5") (pin "R8") (pinfunction "GPMC_AD2/MMC1_DAT2//////GPIO1_2_R8") (pintype "bidirectional"))
    )
    (net (code "102") (name "/MMC1_DAT3") (class "Default")
      (node (ref "U5") (pin "T8") (pinfunction "GPMC_AD3/MMC1_DAT3//////GPIO1_3_T8") (pintype "bidirectional"))
    )
    (net (code "103") (name "/MMC1_DAT4") (class "Default")
      (node (ref "U5") (pin "U8") (pinfunction "GPMC_AD4/MMC1_DAT4//////GPIO1_4_U8") (pintype "bidirectional"))
    )
    (net (code "104") (name "/MMC1_DAT5") (class "Default")
      (node (ref "U5") (pin "V8") (pinfunction "GPMC_AD5/MMC1_DAT5//////GPIO1_5_V8") (pintype "bidirectional"))
    )
    (net (code "105") (name "/MMC1_DAT6") (class "Default")
      (node (ref "U5") (pin "R9") (pinfunction "GPMC_AD6/MMC1_DAT6//////GPIO1_6_R9") (pintype "bidirectional"))
    )
    (net (code "106") (name "/MMC1_DAT7") (class "Default")
      (node (ref "U5") (pin "T9") (pinfunction "GPMC_AD7/MMC1_DAT7//////GPIO1_7_T9") (pintype "bidirectional"))
    )
    (net (code "107") (name "/OSC0_IN") (class "Default")
      (node (ref "C25") (pin "1") (pinfunction "1_1") (pintype "passive"))
      (node (ref "R17") (pin "1") (pinfunction "1_1") (pintype "passive"))
      (node (ref "U5") (pin "V10") (pinfunction "OSC0_IN_V10") (pintype "passive"))
      (node (ref "Y2") (pin "2") (pinfunction "2_2") (pintype "passive"))
    )
    (net (code "108") (name "/OSC0_OUT") (class "Default")
      (node (ref "C26") (pin "1") (pinfunction "1_1") (pintype "passive"))
      (node (ref "R17") (pin "2") (pinfunction "2_2") (pintype "passive"))
      (node (ref "U5") (pin "U11") (pinfunction "OSC0_OUT_U11") (pintype "passive"))
      (node (ref "Y2") (pin "1") (pinfunction "1_1") (pintype "passive"))
    )
    (net (code "109") (name "/OSC1_IN") (class "Default")
      (node (ref "C21") (pin "2") (pinfunction "2_2") (pintype "passive"))
      (node (ref "U5") (pin "A6") (pinfunction "OSC1_IN_A6") (pintype "passive"))
      (node (ref "Y1") (pin "1") (pinfunction "1_1") (pintype "passive"))
    )
    (net (code "110") (name "/OSC1_OUT") (class "Default")
      (node (ref "C22") (pin "2") (pinfunction "2_2") (pintype "passive"))
      (node (ref "U5") (pin "A4") (pinfunction "OSC1_OUT_A4") (pintype "passive"))
      (node (ref "Y1") (pin "4") (pinfunction "4_4") (pintype "passive"))
    )
    (net (code "111") (name "/PMIC_INT") (class "Default")
      (node (ref "U5") (pin "B18") (pinfunction "NNMI_B18") (pintype "input"))
    )
    (net (code "112") (name "/PMIC_PGOOD") (class "Default")
      (node (ref "U16") (pin "2") (pinfunction "A_2") (pintype "input"))
      (node (ref "U5") (pin "B15") (pinfunction "PORZ_B15") (pintype "input"))
    )
    (net (code "113") (name "/PROC_A15") (class "Default")
      (node (ref "R18") (pin "1") (pinfunction "1_1") (pintype "passive"))
      (node (ref "U5") (pin "A15") (pinfunction "EVENT_INTR0/TIMER4/CLKOUT1/SPI1_CS1/PR1PRU1R31_16/EMU2/GPIO0_19_A15") (pintype "bidirectional"))
    )
    (net (code "114") (name "/SYS_RESETn") (class "Default")
      (node (ref "C24") (pin "1") (pinfunction "1_1") (pintype "passive"))
      (node (ref "C30") (pin "1") (pinfunction "1_1") (pintype "passive"))
      (node (ref "P2") (pin "15") (pinfunction "SRST_15") (pintype "passive"))
      (node (ref "R14") (pin "2") (pinfunction "2_2") (pintype "passive"))
      (node (ref "U16") (pin "4") (pinfunction "Y_4") (pintype "open_collector"))
      (node (ref "U5") (pin "A10") (pinfunction "NRESET_INOUT_A10") (pintype "bidirectional"))
    )
    (net (code "115") (name "/TIMER4{slash}GPIO2_2") (class "Default")
      (node (ref "U5") (pin "R7") (pinfunction "GPMC_ADVN_ALE/TIMER4/GPIO2_2_R7") (pintype "bidirectional"))
    )
    (net (code "116") (name "/TIMER5{slash}GPIO2_5") (class "Default")
      (node (ref "U5") (pin "T6") (pinfunction "GPMC_BE0N_CLE/TIMER5/GPIO2_5_T6") (pintype "bidirectional"))
    )
    (net (code "117") (name "/TIMER6{slash}GPIO2_4") (class "Default")
      (node (ref "U5") (pin "U6") (pinfunction "GPMC_WEN/TIMER6/GPIO2_4_U6") (pintype "bidirectional"))
    )
    (net (code "118") (name "/TIMER7{slash}GPIO2_3") (class "Default")
      (node (ref "U5") (pin "T7") (pinfunction "GPMC_OEN_REN/TIMER7/EMU4/GPIO2_3_T7") (pintype "bidirectional"))
    )
    (net (code "119") (name "/U5_R13") (class "Default")
      (node (ref "R160") (pin "1") (pinfunction "1_1") (pintype "passive"))
      (node (ref "U5") (pin "R13") (pinfunction "GPMC_A0/GMII2_TXEN/RGMII2_TCTL/RMII2_TXEN/GPMC_A16/PR1_MII_MT1_CLK/EHRPWM1_TRIPZONE_INPUT/GPIO1_16_R13") (pintype "output"))
    )
    (net (code "120") (name "/U5_T13") (class "Default")
      (node (ref "R161") (pin "1") (pinfunction "1_1") (pintype "passive"))
      (node (ref "U5") (pin "T13") (pinfunction "GPMC_CSN3/MMC2_CMD/PR1_MDIO_DATA/GPIO2_0_T13") (pintype "bidirectional"))
    )
    (net (code "121") (name "/UART4_RXD") (class "Default")
      (node (ref "U5") (pin "T17") (pinfunction "GPMC_WAIT0/GM112_CRS/GPMC_CSN4/RMII2_CRS_DV/MMC1_SDCD/PR1_MII1_RXDV/UART4_RXD/GPIO0_30_T17") (pintype "input"))
    )
    (net (code "122") (name "/UART4_TXD") (class "Default")
      (node (ref "U5") (pin "U17") (pinfunction "GPMC_WPN/GMII2_RXERR/GPMC_CSN5/RMII2_RXERR/MMC2_SDCD/PR1_MDIO_MDCLK/UART4_TXD/GPIO0_31_U17") (pintype "output"))
    )
    (net (code "123") (name "/USB_~{FLT}") (class "Default")
      (node (ref "U5") (pin "T16") (pinfunction "GPMC_A10/GMII2_RXD1/RGMII2_RD1/RMII2_RXD1/GPMC_A26/PR1_MII1_CRS/MCASP0_AXR0/GPIO1_26_T16") (pintype "input"))
    )
    (net (code "124") (name "/USR0") (class "Default")
      (node (ref "U5") (pin "V15") (pinfunction "GPMC_A5/GMII2_TXD0/RGMII2_TD0/RMII2_TXD0/GPMC_A21/PR1_MII1_RXD3/EQEP1B_IN/GPIO1_21_V15") (pintype "output"))
    )
    (net (code "125") (name "/USR1") (class "Default")
      (node (ref "U5") (pin "U15") (pinfunction "GPMC_A6/GMII2_TXCLK/RGMII2_TCLK/MMC2_DAT4/GPMC_A22/PR1_MII1_RXD2/EQEP1_INDEX/GPIO1_22_U15") (pintype "output"))
    )
    (net (code "126") (name "/USR2") (class "Default")
      (node (ref "U5") (pin "T15") (pinfunction "GPMC_A7/GMII2_RXCLK/RGMII2_RCLK/MMC2_DAT5/GPMC_A23/PR1_MII1_RXD1/EQEP1_STROBE/GPIO1_23_T15") (pintype "output"))
    )
    (net (code "127") (name "/USR3") (class "Default")
      (node (ref "U5") (pin "V16") (pinfunction "GPMC_A8/GMII2_RXD3/RGMII2_RD3/MMC2_DAT6/GPMC_A24/PR1_MII1_RXD0/MCASP0_ACLKX/GPIO1_24_V16") (pintype "output"))
    )
    (net (code "129") (name "/XDMA_EVENT_INTR0") (class "Default")
      (node (ref "P2") (pin "17") (pinfunction "EMU2_17") (pintype "passive"))
      (node (ref "R18") (pin "2") (pinfunction "2_2") (pintype "passive"))
      (node (ref "U6") (pin "1") (pinfunction "CLK_1") (pintype "input"))
    )
    (net (code "130") (name "/eMMC_RSTn") (class "Default")
      (node (ref "R162") (pin "2") (pinfunction "2_2") (pintype "passive"))
    )
    (net (code "135") (name "DDR_VREF") (class "Default")
      (node (ref "C28") (pin "1") (pinfunction "1_1") (pintype "passive"))
      (node (ref "U5") (pin "J4") (pinfunction "VREFSSTL_J4") (pintype "passive"))
    )
    (net (code "136") (name "DGND") (class "Default")
      (node (ref "C158") (pin "2") (pinfunction "2_2") (pintype "passive"))
      (node (ref "C159") (pin "2") (pinfunction "2_2") (pintype "passive"))
      (node (ref "C24") (pin "2") (pinfunction "2_2") (pintype "passive"))
      (node (ref "C27") (pin "2") (pinfunction "2_2") (pintype "passive"))
      (node (ref "C28") (pin "2") (pinfunction "2_2") (pintype "passive"))
      (node (ref "C29") (pin "2") (pinfunction "2_2") (pintype "passive"))
      (node (ref "C30") (pin "2") (pinfunction "2_2") (pintype "passive"))
      (node (ref "P2") (pin "10") (pinfunction "GND_10") (pintype "power_in"))
      (node (ref "P2") (pin "12") (pinfunction "GND_12") (pintype "power_in"))
      (node (ref "P2") (pin "16") (pinfunction "GND_16") (pintype "power_in"))
      (node (ref "P2") (pin "20") (pinfunction "GND_20") (pintype "power_in"))
      (node (ref "P2") (pin "4") (pinfunction "TDIS_4") (pintype "passive"))
      (node (ref "P2") (pin "8") (pinfunction "GND_8") (pintype "power_in"))
      (node (ref "R22") (pin "1") (pinfunction "1_1") (pintype "passive"))
      (node (ref "R25") (pin "2") (pinfunction "2_2") (pintype "passive"))
      (node (ref "R29") (pin "2") (pinfunction "2_2") (pintype "passive"))
      (node (ref "R30") (pin "1") (pinfunction "1_1") (pintype "passive"))
      (node (ref "U16") (pin "3") (pinfunction "GND_3") (pintype "power_in"))
      (node (ref "U3") (pin "3") (pinfunction "GND_3") (pintype "power_in"))
      (node (ref "U6") (pin "4") (pinfunction "GND_4") (pintype "power_in"))
      (node (ref "Y4") (pin "2") (pinfunction "GND_2") (pintype "power_in"))
    )
    (net (code "137") (name "GND_OSC0") (class "Default")
      (node (ref "C25") (pin "2") (pinfunction "2_2") (pintype "passive"))
      (node (ref "C26") (pin "2") (pinfunction "2_2") (pintype "passive"))
      (node (ref "R29") (pin "1") (pinfunction "1_1") (pintype "passive"))
      (node (ref "U5") (pin "V11") (pinfunction "VSS_OSC0_V11") (pintype "power_in"))
    )
    (net (code "138") (name "Net-(U3-A)") (class "Default")
      (node (ref "U3") (pin "2") (pinfunction "A_2") (pintype "input"))
      (node (ref "U5") (pin "R14") (pinfunction "GPMC_A4/GMII2_TXD1/RGMII2_TD1/RMII2_TXD1/GPMC_A20/PR1_MII1_TXD0/EQEP1A_IN/GPIO1_20_R14") (pintype "output"))
    )
    (net (code "139") (name "Net-(U3-Y)") (class "Default")
      (node (ref "R162") (pin "1") (pinfunction "1_1") (pintype "passive"))
      (node (ref "U3") (pin "4") (pinfunction "Y_4") (pintype "open_collector"))
    )
    (net (code "140") (name "Net-(U6-Q)") (class "Default")
      (node (ref "R21") (pin "1") (pinfunction "1_1") (pintype "passive"))
      (node (ref "U6") (pin "5") (pinfunction "Q_5") (pintype "output"))
    )
    (net (code "141") (name "VDD_3V3A") (class "Default")
      (node (ref "C158") (pin "1") (pinfunction "1_1") (pintype "passive"))
      (node (ref "C159") (pin "1") (pinfunction "1_1") (pintype "passive"))
      (node (ref "C27") (pin "1") (pinfunction "1_1") (pintype "passive"))
      (node (ref "R14") (pin "1") (pinfunction "1_1") (pintype "passive"))
      (node (ref "U3") (pin "5") (pinfunction "VCC_5") (pintype "power_in"))
      (node (ref "U6") (pin "6") (pinfunction "~{CLR}_6") (pintype "input"))
      (node (ref "U6") (pin "7") (pinfunction "~{PRE}_7") (pintype "input"))
      (node (ref "U6") (pin "8") (pinfunction "VCC_8") (pintype "power_in"))
      (node (ref "Y4") (pin "4") (pinfunction "VCC_4") (pintype "power_in"))
    )
    (net (code "142") (name "VDD_3V3B") (class "Default")
      (node (ref "C29") (pin "1") (pinfunction "1_1") (pintype "passive"))
      (node (ref "P2") (pin "5") (pinfunction "TVDD_5") (pintype "passive"))
      (node (ref "R23") (pin "1") (pinfunction "1_1") (pintype "passive"))
      (node (ref "R24") (pin "1") (pinfunction "1_1") (pintype "passive"))
    )
    (net (code "143") (name "VIO") (class "Default")
      (node (ref "U16") (pin "5") (pinfunction "VCC_5") (pintype "power_in"))
    )
    (net (code "144") (name "unconnected-(P2-NC-Pad6)") (class "Default")
      (node (ref "P2") (pin "6") (pinfunction "NC_6") (pintype "passive+no_connect"))
    )
    (net (code "145") (name "unconnected-(U3-NC-Pad1)") (class "Default")
      (node (ref "U3") (pin "1") (pinfunction "NC_1") (pintype "passive+no_connect"))
    )
    (net (code "146") (name "unconnected-(U16-NC-Pad1)") (class "Default")
      (node (ref "U16") (pin "1") (pinfunction "NC_1") (pintype "passive"))
    )
    (net (code "147") (name "unconnected-(Y1-Pad2)") (class "Default")
      (node (ref "Y1") (pin "2") (pinfunction "2_2") (pintype "passive"))
    )
    (net (code "148") (name "unconnected-(Y1-Pad3)") (class "Default")
      (node (ref "Y1") (pin "3") (pinfunction "3_3") (pintype "passive"))
    )
  )
)
